# P04_BCS1_Core_Connector.net
KiCad netlist of a schematic drawn in Altium Designer
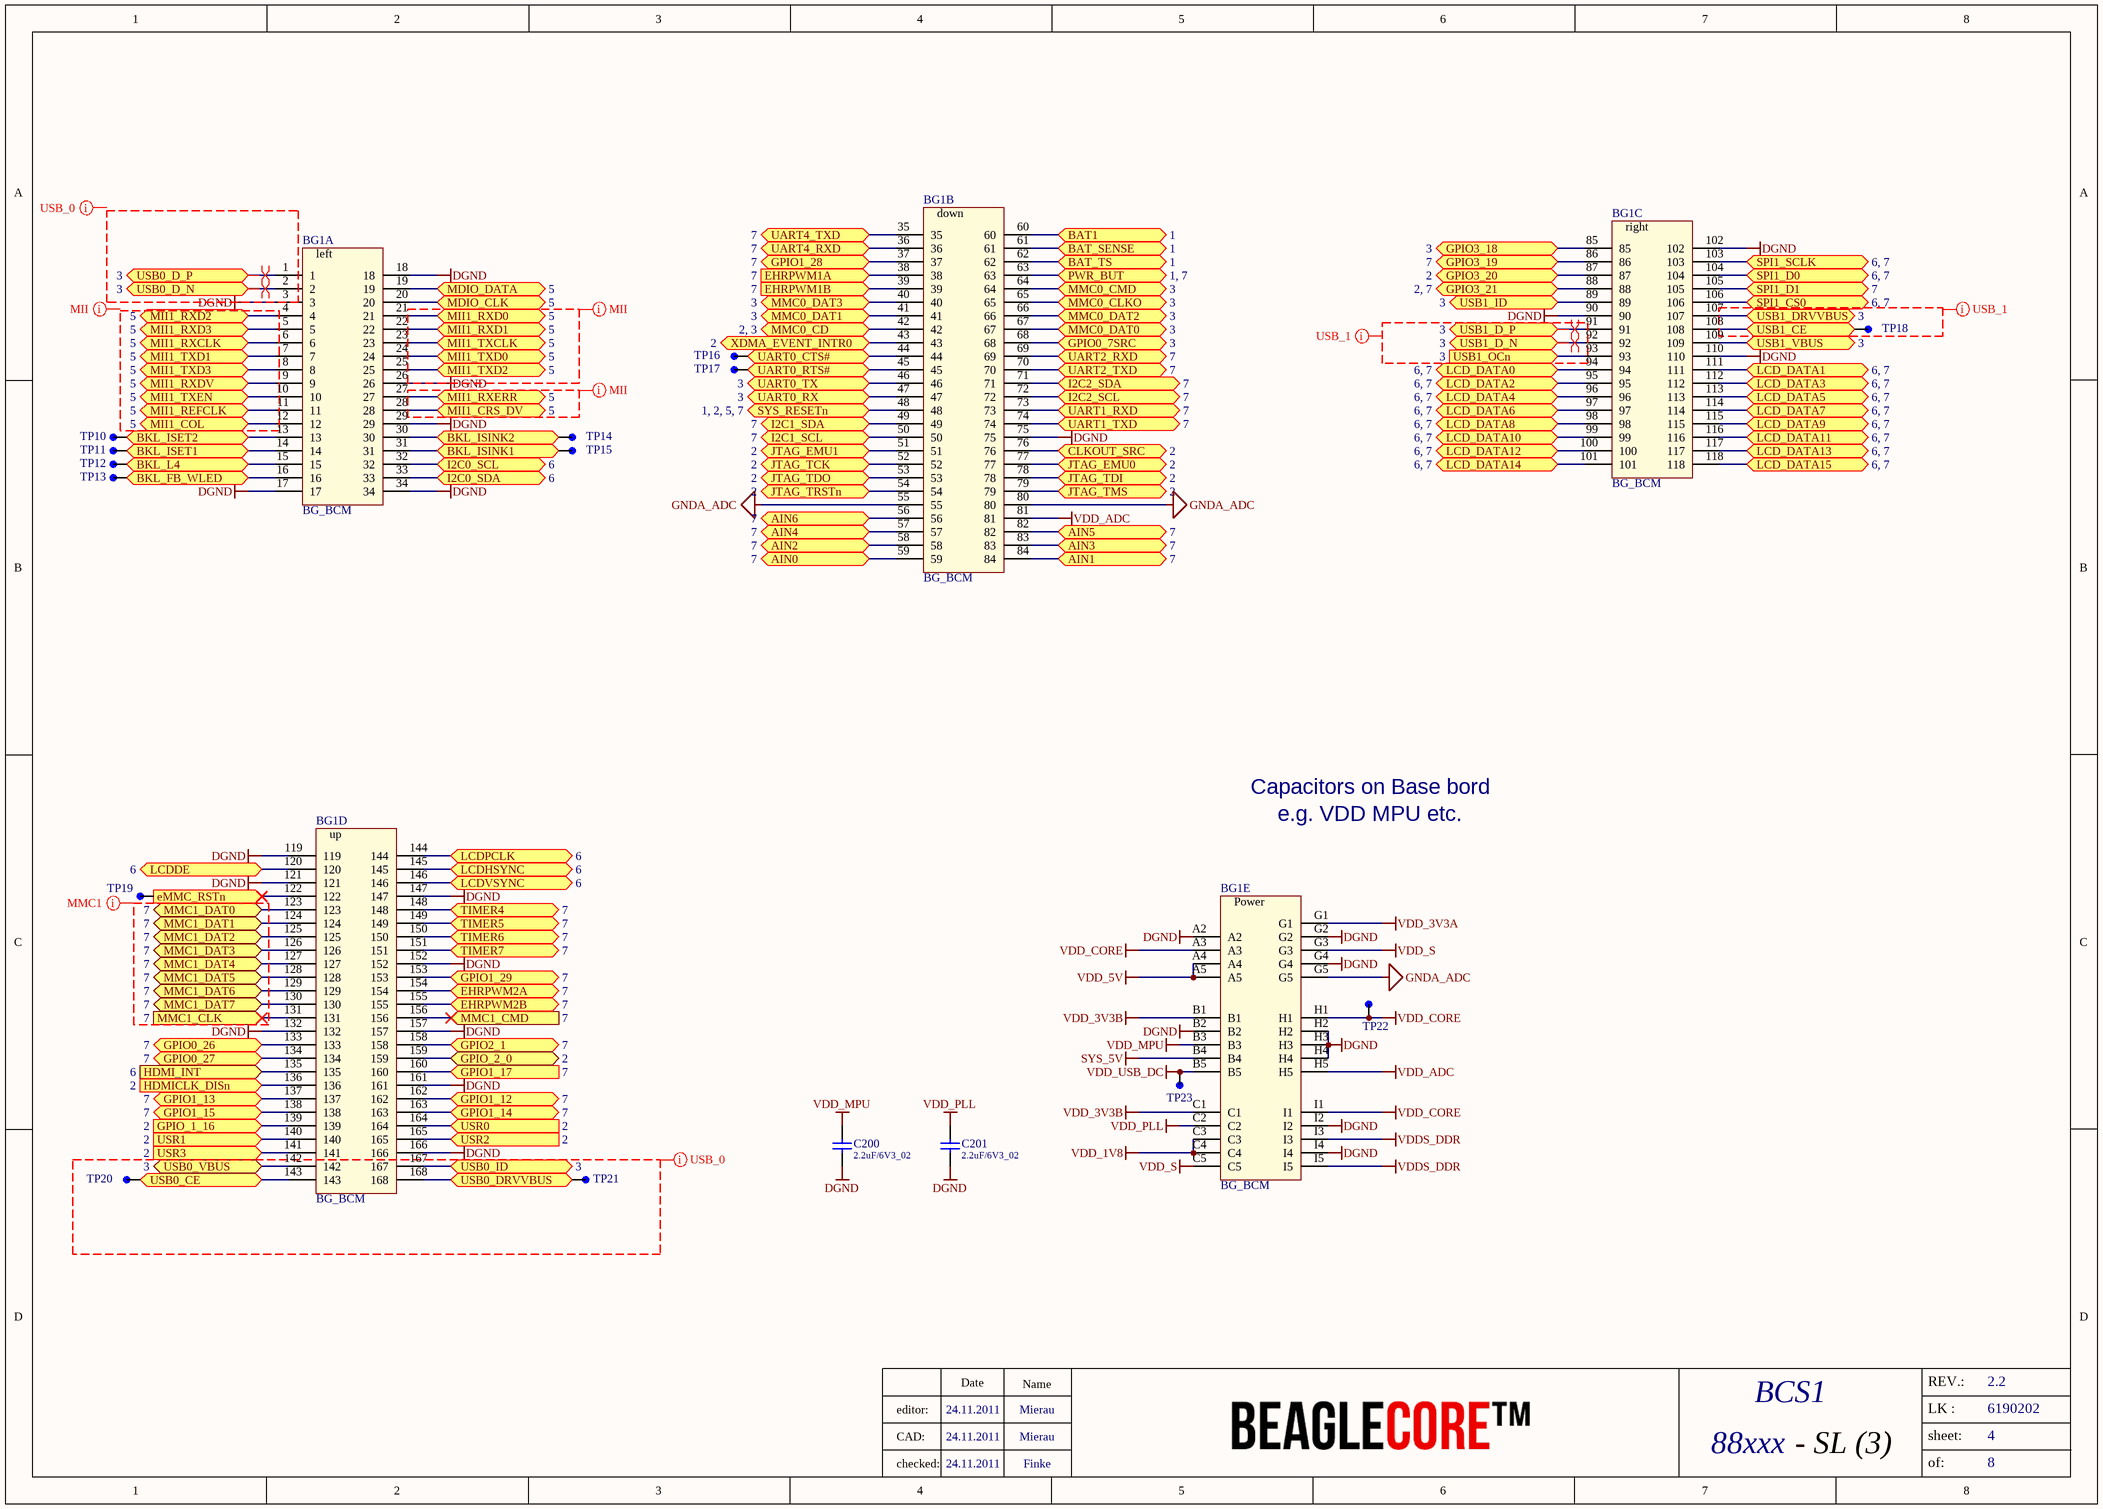
[diagram p0: P04_BCS1_Core Connector.SchDoc]

(export (version "E")
  (design (tool "Eeschema 10.0.6"))
  (components
    (comp (ref "BG1")
      (value "BG_BCM")
      (footprint "BG_BCM")
      (description "Beaglecore")
      (libsource (lib "*") (part "BG_BCM"))
    )
    (comp (ref "C200")
      (value "2.2uF/6V3_02")
      (footprint "CC1005-0402")
      (description "Capacitor 0402;  6V3;  X5R")
      (libsource (lib "*") (part "C2.2uF/6V3_02"))
    )
    (comp (ref "C201")
      (value "2.2uF/6V3_02")
      (footprint "CC1005-0402")
      (description "Capacitor 0402;  6V3;  X5R")
      (libsource (lib "*") (part "C2.2uF/6V3_02"))
    )
    (comp (ref "TP10")
      (value "TP THT")
      (footprint "TP mit 0.8mm Bohrung")
      (description "Testpunkt rund mit Bohrung D=0.8mm")
      (libsource (lib "*") (part "TP1.6 mit Bohrung 0.8"))
    )
    (comp (ref "TP11")
      (value "TP THT")
      (footprint "TP mit 0.8mm Bohrung")
      (description "Testpunkt rund mit Bohrung D=0.8mm")
      (libsource (lib "*") (part "TP1.6 mit Bohrung 0.8"))
    )
    (comp (ref "TP12")
      (value "TP THT")
      (footprint "TP mit 0.8mm Bohrung")
      (description "Testpunkt rund mit Bohrung D=0.8mm")
      (libsource (lib "*") (part "TP1.6 mit Bohrung 0.8"))
    )
    (comp (ref "TP13")
      (value "TP THT")
      (footprint "TP mit 0.8mm Bohrung")
      (description "Testpunkt rund mit Bohrung D=0.8mm")
      (libsource (lib "*") (part "TP1.6 mit Bohrung 0.8"))
    )
    (comp (ref "TP14")
      (value "TP THT")
      (footprint "TP mit 0.8mm Bohrung")
      (description "Testpunkt rund mit Bohrung D=0.8mm")
      (libsource (lib "*") (part "TP1.6 mit Bohrung 0.8"))
    )
    (comp (ref "TP15")
      (value "TP THT")
      (footprint "TP mit 0.8mm Bohrung")
      (description "Testpunkt rund mit Bohrung D=0.8mm")
      (libsource (lib "*") (part "TP1.6 mit Bohrung 0.8"))
    )
    (comp (ref "TP16")
      (value "TP THT")
      (footprint "TP mit 0.8mm Bohrung")
      (description "Testpunkt rund mit Bohrung D=0.8mm")
      (libsource (lib "*") (part "TP1.6 mit Bohrung 0.8"))
    )
    (comp (ref "TP17")
      (value "TP THT")
      (footprint "TP mit 0.8mm Bohrung")
      (description "Testpunkt rund mit Bohrung D=0.8mm")
      (libsource (lib "*") (part "TP1.6 mit Bohrung 0.8"))
    )
    (comp (ref "TP18")
      (value "TP THT")
      (footprint "TP mit 0.8mm Bohrung")
      (description "Testpunkt rund mit Bohrung D=0.8mm")
      (libsource (lib "*") (part "TP1.6 mit Bohrung 0.8"))
    )
    (comp (ref "TP19")
      (value "TP THT")
      (footprint "TP mit 0.8mm Bohrung")
      (description "Testpunkt rund mit Bohrung D=0.8mm")
      (fields (field (name "ERSTELLT VON") "Finke"))
      (libsource (lib "*") (part "TP1.6 mit Bohrung 0.8"))
    )
    (comp (ref "TP20")
      (value "TP THT")
      (footprint "TP mit 0.8mm Bohrung")
      (description "Testpunkt rund mit Bohrung D=0.8mm")
      (libsource (lib "*") (part "TP1.6 mit Bohrung 0.8"))
    )
    (comp (ref "TP21")
      (value "TP THT")
      (footprint "TP mit 0.8mm Bohrung")
      (description "Testpunkt rund mit Bohrung D=0.8mm")
      (libsource (lib "*") (part "TP1.6 mit Bohrung 0.8"))
    )
    (comp (ref "TP22")
      (value "TP THT")
      (footprint "TP mit 0.8mm Bohrung")
      (description "Testpunkt rund mit Bohrung D=0.8mm")
      (libsource (lib "*") (part "TP1.6 mit Bohrung 0.8"))
    )
    (comp (ref "TP23")
      (value "TP THT")
      (footprint "TP mit 0.8mm Bohrung")
      (description "Testpunkt rund mit Bohrung D=0.8mm")
      (libsource (lib "*") (part "TP1.6 mit Bohrung 0.8"))
    )
  )
  (nets
    (net (code "1") (name "/AIN0") (class "Default")
      (node (ref "BG1") (pin "59") (pinfunction "59_59") (pintype "passive"))
    )
    (net (code "2") (name "/AIN1") (class "Default")
      (node (ref "BG1") (pin "84") (pinfunction "84_84") (pintype "passive"))
    )
    (net (code "3") (name "/AIN2") (class "Default")
      (node (ref "BG1") (pin "58") (pinfunction "58_58") (pintype "passive"))
    )
    (net (code "4") (name "/AIN3") (class "Default")
      (node (ref "BG1") (pin "83") (pinfunction "83_83") (pintype "passive"))
    )
    (net (code "5") (name "/AIN4") (class "Default")
      (node (ref "BG1") (pin "57") (pinfunction "57_57") (pintype "passive"))
    )
    (net (code "6") (name "/AIN5") (class "Default")
      (node (ref "BG1") (pin "82") (pinfunction "82_82") (pintype "passive"))
    )
    (net (code "7") (name "/AIN6") (class "Default")
      (node (ref "BG1") (pin "56") (pinfunction "56_56") (pintype "passive"))
    )
    (net (code "8") (name "/BAT1") (class "Default")
      (node (ref "BG1") (pin "60") (pinfunction "60_60") (pintype "passive"))
    )
    (net (code "9") (name "/BAT_SENSE") (class "Default")
      (node (ref "BG1") (pin "61") (pinfunction "61_61") (pintype "passive"))
    )
    (net (code "10") (name "/BAT_TS") (class "Default")
      (node (ref "BG1") (pin "62") (pinfunction "62_62") (pintype "passive"))
    )
    (net (code "11") (name "/BKL_FB_WLED") (class "Default")
      (node (ref "BG1") (pin "16") (pinfunction "16_16") (pintype "passive"))
      (node (ref "TP13") (pin "1") (pinfunction "Pin_1") (pintype "passive"))
    )
    (net (code "12") (name "/BKL_ISET1") (class "Default")
      (node (ref "BG1") (pin "14") (pinfunction "14_14") (pintype "passive"))
      (node (ref "TP11") (pin "1") (pinfunction "Pin_1") (pintype "passive"))
    )
    (net (code "13") (name "/BKL_ISET2") (class "Default")
      (node (ref "BG1") (pin "13") (pinfunction "13_13") (pintype "passive"))
      (node (ref "TP10") (pin "1") (pinfunction "Pin_1") (pintype "passive"))
    )
    (net (code "14") (name "/BKL_ISINK1") (class "Default")
      (node (ref "BG1") (pin "31") (pinfunction "31_31") (pintype "passive"))
      (node (ref "TP15") (pin "1") (pinfunction "Pin_1") (pintype "passive"))
    )
    (net (code "15") (name "/BKL_ISINK2") (class "Default")
      (node (ref "BG1") (pin "30") (pinfunction "30_30") (pintype "passive"))
      (node (ref "TP14") (pin "1") (pinfunction "Pin_1") (pintype "passive"))
    )
    (net (code "16") (name "/BKL_L4") (class "Default")
      (node (ref "BG1") (pin "15") (pinfunction "15_15") (pintype "passive"))
      (node (ref "TP12") (pin "1") (pinfunction "Pin_1") (pintype "passive"))
    )
    (net (code "17") (name "/CLKOUT_SRC") (class "Default")
      (node (ref "BG1") (pin "76") (pinfunction "76_76") (pintype "passive"))
    )
    (net (code "18") (name "/EHRPWM1A") (class "Default")
      (node (ref "BG1") (pin "38") (pinfunction "38_38") (pintype "passive"))
    )
    (net (code "19") (name "/EHRPWM1B") (class "Default")
      (node (ref "BG1") (pin "39") (pinfunction "39_39") (pintype "passive"))
    )
    (net (code "20") (name "/EHRPWM2A") (class "Default")
      (node (ref "BG1") (pin "154") (pinfunction "154_154") (pintype "passive"))
    )
    (net (code "21") (name "/EHRPWM2B") (class "Default")
      (node (ref "BG1") (pin "155") (pinfunction "155_155") (pintype "passive"))
    )
    (net (code "22") (name "/GPIO0_7SRC") (class "Default")
      (node (ref "BG1") (pin "68") (pinfunction "68_68") (pintype "passive"))
    )
    (net (code "23") (name "/GPIO0_26") (class "Default")
      (node (ref "BG1") (pin "133") (pinfunction "133_133") (pintype "passive"))
    )
    (net (code "24") (name "/GPIO0_27") (class "Default")
      (node (ref "BG1") (pin "134") (pinfunction "134_134") (pintype "passive"))
    )
    (net (code "25") (name "/GPIO1_12") (class "Default")
      (node (ref "BG1") (pin "162") (pinfunction "162_162") (pintype "passive"))
    )
    (net (code "26") (name "/GPIO1_13") (class "Default")
      (node (ref "BG1") (pin "137") (pinfunction "137_137") (pintype "passive"))
    )
    (net (code "27") (name "/GPIO1_14") (class "Default")
      (node (ref "BG1") (pin "163") (pinfunction "163_163") (pintype "passive"))
    )
    (net (code "28") (name "/GPIO1_15") (class "Default")
      (node (ref "BG1") (pin "138") (pinfunction "138_138") (pintype "passive"))
    )
    (net (code "29") (name "/GPIO1_17") (class "Default")
      (node (ref "BG1") (pin "160") (pinfunction "160_160") (pintype "passive"))
    )
    (net (code "30") (name "/GPIO1_28") (class "Default")
      (node (ref "BG1") (pin "37") (pinfunction "37_37") (pintype "passive"))
    )
    (net (code "31") (name "/GPIO1_29") (class "Default")
      (node (ref "BG1") (pin "153") (pinfunction "153_153") (pintype "passive"))
    )
    (net (code "32") (name "/GPIO2_1") (class "Default")
      (node (ref "BG1") (pin "158") (pinfunction "158_158") (pintype "passive"))
    )
    (net (code "33") (name "/GPIO3_18") (class "Default")
      (node (ref "BG1") (pin "85") (pinfunction "85_85") (pintype "passive"))
    )
    (net (code "34") (name "/GPIO3_19") (class "Default")
      (node (ref "BG1") (pin "86") (pinfunction "86_86") (pintype "passive"))
    )
    (net (code "35") (name "/GPIO3_20") (class "Default")
      (node (ref "BG1") (pin "87") (pinfunction "87_87") (pintype "passive"))
    )
    (net (code "36") (name "/GPIO3_21") (class "Default")
      (node (ref "BG1") (pin "88") (pinfunction "88_88") (pintype "passive"))
    )
    (net (code "37") (name "/GPIO_1_16") (class "Default")
      (node (ref "BG1") (pin "139") (pinfunction "139_139") (pintype "passive"))
    )
    (net (code "38") (name "/GPIO_2_0") (class "Default")
      (node (ref "BG1") (pin "159") (pinfunction "159_159") (pintype "passive"))
    )
    (net (code "39") (name "/HDMICLK_DISn") (class "Default")
      (node (ref "BG1") (pin "136") (pinfunction "136_136") (pintype "passive"))
    )
    (net (code "40") (name "/HDMI_INT") (class "Default")
      (node (ref "BG1") (pin "135") (pinfunction "135_135") (pintype "passive"))
    )
    (net (code "41") (name "/I2C0_SCL") (class "Default")
      (node (ref "BG1") (pin "32") (pinfunction "32_32") (pintype "passive"))
    )
    (net (code "42") (name "/I2C0_SDA") (class "Default")
      (node (ref "BG1") (pin "33") (pinfunction "33_33") (pintype "passive"))
    )
    (net (code "43") (name "/I2C1_SCL") (class "Default")
      (node (ref "BG1") (pin "50") (pinfunction "50_50") (pintype "passive"))
    )
    (net (code "44") (name "/I2C1_SDA") (class "Default")
      (node (ref "BG1") (pin "49") (pinfunction "49_49") (pintype "passive"))
    )
    (net (code "45") (name "/I2C2_SCL") (class "Default")
      (node (ref "BG1") (pin "72") (pinfunction "72_72") (pintype "passive"))
    )
    (net (code "46") (name "/I2C2_SDA") (class "Default")
      (node (ref "BG1") (pin "71") (pinfunction "71_71") (pintype "passive"))
    )
    (net (code "47") (name "/JTAG_EMU0") (class "Default")
      (node (ref "BG1") (pin "77") (pinfunction "77_77") (pintype "passive"))
    )
    (net (code "48") (name "/JTAG_EMU1") (class "Default")
      (node (ref "BG1") (pin "51") (pinfunction "51_51") (pintype "passive"))
    )
    (net (code "49") (name "/JTAG_TCK") (class "Default")
      (node (ref "BG1") (pin "52") (pinfunction "52_52") (pintype "passive"))
    )
    (net (code "50") (name "/JTAG_TDI") (class "Default")
      (node (ref "BG1") (pin "78") (pinfunction "78_78") (pintype "passive"))
    )
    (net (code "51") (name "/JTAG_TDO") (class "Default")
      (node (ref "BG1") (pin "53") (pinfunction "53_53") (pintype "passive"))
    )
    (net (code "52") (name "/JTAG_TMS") (class "Default")
      (node (ref "BG1") (pin "79") (pinfunction "79_79") (pintype "passive"))
    )
    (net (code "53") (name "/JTAG_TRSTn") (class "Default")
      (node (ref "BG1") (pin "54") (pinfunction "54_54") (pintype "passive"))
    )
    (net (code "54") (name "/LCDDE") (class "Default")
      (node (ref "BG1") (pin "120") (pinfunction "120_120") (pintype "passive"))
    )
    (net (code "55") (name "/LCDHSYNC") (class "Default")
      (node (ref "BG1") (pin "145") (pinfunction "145_145") (pintype "passive"))
    )
    (net (code "56") (name "/LCDPCLK") (class "Default")
      (node (ref "BG1") (pin "144") (pinfunction "144_144") (pintype "passive"))
    )
    (net (code "57") (name "/LCDVSYNC") (class "Default")
      (node (ref "BG1") (pin "146") (pinfunction "146_146") (pintype "passive"))
    )
    (net (code "58") (name "/LCD_DATA0") (class "Default")
      (node (ref "BG1") (pin "94") (pinfunction "94_94") (pintype "passive"))
    )
    (net (code "59") (name "/LCD_DATA1") (class "Default")
      (node (ref "BG1") (pin "111") (pinfunction "111_111") (pintype "passive"))
    )
    (net (code "60") (name "/LCD_DATA2") (class "Default")
      (node (ref "BG1") (pin "95") (pinfunction "95_95") (pintype "passive"))
    )
    (net (code "61") (name "/LCD_DATA3") (class "Default")
      (node (ref "BG1") (pin "112") (pinfunction "112_112") (pintype "passive"))
    )
    (net (code "62") (name "/LCD_DATA4") (class "Default")
      (node (ref "BG1") (pin "96") (pinfunction "96_96") (pintype "passive"))
    )
    (net (code "63") (name "/LCD_DATA5") (class "Default")
      (node (ref "BG1") (pin "113") (pinfunction "113_113") (pintype "passive"))
    )
    (net (code "64") (name "/LCD_DATA6") (class "Default")
      (node (ref "BG1") (pin "97") (pinfunction "97_97") (pintype "passive"))
    )
    (net (code "65") (name "/LCD_DATA7") (class "Default")
      (node (ref "BG1") (pin "114") (pinfunction "114_114") (pintype "passive"))
    )
    (net (code "66") (name "/LCD_DATA8") (class "Default")
      (node (ref "BG1") (pin "98") (pinfunction "98_98") (pintype "passive"))
    )
    (net (code "67") (name "/LCD_DATA9") (class "Default")
      (node (ref "BG1") (pin "115") (pinfunction "115_115") (pintype "passive"))
    )
    (net (code "68") (name "/LCD_DATA10") (class "Default")
      (node (ref "BG1") (pin "99") (pinfunction "99_99") (pintype "passive"))
    )
    (net (code "69") (name "/LCD_DATA11") (class "Default")
      (node (ref "BG1") (pin "116") (pinfunction "116_116") (pintype "passive"))
    )
    (net (code "70") (name "/LCD_DATA12") (class "Default")
      (node (ref "BG1") (pin "100") (pinfunction "100_100") (pintype "passive"))
    )
    (net (code "71") (name "/LCD_DATA13") (class "Default")
      (node (ref "BG1") (pin "117") (pinfunction "117_117") (pintype "passive"))
    )
    (net (code "72") (name "/LCD_DATA14") (class "Default")
      (node (ref "BG1") (pin "101") (pinfunction "101_101") (pintype "passive"))
    )
    (net (code "73") (name "/LCD_DATA15") (class "Default")
      (node (ref "BG1") (pin "118") (pinfunction "118_118") (pintype "passive"))
    )
    (net (code "74") (name "/MDIO_CLK") (class "Default")
      (node (ref "BG1") (pin "20") (pinfunction "20_20") (pintype "passive"))
    )
    (net (code "75") (name "/MDIO_DATA") (class "Default")
      (node (ref "BG1") (pin "19") (pinfunction "19_19") (pintype "passive"))
    )
    (net (code "76") (name "/MII1_COL") (class "Default")
      (node (ref "BG1") (pin "12") (pinfunction "12_12") (pintype "passive"))
    )
    (net (code "77") (name "/MII1_CRS_DV") (class "Default")
      (node (ref "BG1") (pin "28") (pinfunction "28_28") (pintype "passive"))
    )
    (net (code "78") (name "/MII1_REFCLK") (class "Default")
      (node (ref "BG1") (pin "11") (pinfunction "11_11") (pintype "passive"))
    )
    (net (code "79") (name "/MII1_RXCLK") (class "Default")
      (node (ref "BG1") (pin "6") (pinfunction "6_6") (pintype "passive"))
    )
    (net (code "80") (name "/MII1_RXD0") (class "Default")
      (node (ref "BG1") (pin "21") (pinfunction "21_21") (pintype "passive"))
    )
    (net (code "81") (name "/MII1_RXD1") (class "Default")
      (node (ref "BG1") (pin "22") (pinfunction "22_22") (pintype "passive"))
    )
    (net (code "82") (name "/MII1_RXD2") (class "Default")
      (node (ref "BG1") (pin "4") (pinfunction "4_4") (pintype "passive"))
    )
    (net (code "83") (name "/MII1_RXD3") (class "Default")
      (node (ref "BG1") (pin "5") (pinfunction "5_5") (pintype "passive"))
    )
    (net (code "84") (name "/MII1_RXDV") (class "Default")
      (node (ref "BG1") (pin "9") (pinfunction "9_9") (pintype "passive"))
    )
    (net (code "85") (name "/MII1_RXERR") (class "Default")
      (node (ref "BG1") (pin "27") (pinfunction "27_27") (pintype "passive"))
    )
    (net (code "86") (name "/MII1_TXCLK") (class "Default")
      (node (ref "BG1") (pin "23") (pinfunction "23_23") (pintype "passive"))
    )
    (net (code "87") (name "/MII1_TXD0") (class "Default")
      (node (ref "BG1") (pin "24") (pinfunction "24_24") (pintype "passive"))
    )
    (net (code "88") (name "/MII1_TXD1") (class "Default")
      (node (ref "BG1") (pin "7") (pinfunction "7_7") (pintype "passive"))
    )
    (net (code "89") (name "/MII1_TXD2") (class "Default")
      (node (ref "BG1") (pin "25") (pinfunction "25_25") (pintype "passive"))
    )
    (net (code "90") (name "/MII1_TXD3") (class "Default")
      (node (ref "BG1") (pin "8") (pinfunction "8_8") (pintype "passive"))
    )
    (net (code "91") (name "/MII1_TXEN") (class "Default")
      (node (ref "BG1") (pin "10") (pinfunction "10_10") (pintype "passive"))
    )
    (net (code "92") (name "/MMC0_CD") (class "Default")
      (node (ref "BG1") (pin "42") (pinfunction "42_42") (pintype "passive"))
    )
    (net (code "93") (name "/MMC0_CLKO") (class "Default")
      (node (ref "BG1") (pin "65") (pinfunction "65_65") (pintype "passive"))
    )
    (net (code "94") (name "/MMC0_CMD") (class "Default")
      (node (ref "BG1") (pin "64") (pinfunction "64_64") (pintype "passive"))
    )
    (net (code "95") (name "/MMC0_DAT0") (class "Default")
      (node (ref "BG1") (pin "67") (pinfunction "67_67") (pintype "passive"))
    )
    (net (code "96") (name "/MMC0_DAT1") (class "Default")
      (node (ref "BG1") (pin "41") (pinfunction "41_41") (pintype "passive"))
    )
    (net (code "97") (name "/MMC0_DAT2") (class "Default")
      (node (ref "BG1") (pin "66") (pinfunction "66_66") (pintype "passive"))
    )
    (net (code "98") (name "/MMC0_DAT3") (class "Default")
      (node (ref "BG1") (pin "40") (pinfunction "40_40") (pintype "passive"))
    )
    (net (code "99") (name "/MMC1_CLK") (class "Default")
      (node (ref "BG1") (pin "131") (pinfunction "131_131") (pintype "passive+no_connect"))
    )
    (net (code "100") (name "/MMC1_CMD") (class "Default")
      (node (ref "BG1") (pin "156") (pinfunction "156_156") (pintype "passive+no_connect"))
    )
    (net (code "101") (name "/MMC1_DAT0") (class "Default")
      (node (ref "BG1") (pin "123") (pinfunction "123_123") (pintype "passive"))
    )
    (net (code "102") (name "/MMC1_DAT1") (class "Default")
      (node (ref "BG1") (pin "124") (pinfunction "124_124") (pintype "passive"))
    )
    (net (code "103") (name "/MMC1_DAT2") (class "Default")
      (node (ref "BG1") (pin "125") (pinfunction "125_125") (pintype "passive"))
    )
    (net (code "104") (name "/MMC1_DAT3") (class "Default")
      (node (ref "BG1") (pin "126") (pinfunction "126_126") (pintype "passive"))
    )
    (net (code "105") (name "/MMC1_DAT4") (class "Default")
      (node (ref "BG1") (pin "127") (pinfunction "127_127") (pintype "passive"))
    )
    (net (code "106") (name "/MMC1_DAT5") (class "Default")
      (node (ref "BG1") (pin "128") (pinfunction "128_128") (pintype "passive"))
    )
    (net (code "107") (name "/MMC1_DAT6") (class "Default")
      (node (ref "BG1") (pin "129") (pinfunction "129_129") (pintype "passive"))
    )
    (net (code "108") (name "/MMC1_DAT7") (class "Default")
      (node (ref "BG1") (pin "130") (pinfunction "130_130") (pintype "passive"))
    )
    (net (code "109") (name "/PWR_BUT") (class "Default")
      (node (ref "BG1") (pin "63") (pinfunction "63_63") (pintype "passive"))
    )
    (net (code "110") (name "/SPI1_CS0") (class "Default")
      (node (ref "BG1") (pin "106") (pinfunction "106_106") (pintype "passive"))
    )
    (net (code "111") (name "/SPI1_D0") (class "Default")
      (node (ref "BG1") (pin "104") (pinfunction "104_104") (pintype "passive"))
    )
    (net (code "112") (name "/SPI1_D1") (class "Default")
      (node (ref "BG1") (pin "105") (pinfunction "105_105") (pintype "passive"))
    )
    (net (code "113") (name "/SPI1_SCLK") (class "Default")
      (node (ref "BG1") (pin "103") (pinfunction "103_103") (pintype "passive"))
    )
    (net (code "114") (name "/SYS_RESETn") (class "Default")
      (node (ref "BG1") (pin "48") (pinfunction "48_48") (pintype "passive"))
    )
    (net (code "115") (name "/TIMER4") (class "Default")
      (node (ref "BG1") (pin "148") (pinfunction "148_148") (pintype "passive"))
    )
    (net (code "116") (name "/TIMER5") (class "Default")
      (node (ref "BG1") (pin "149") (pinfunction "149_149") (pintype "passive"))
    )
    (net (code "117") (name "/TIMER6") (class "Default")
      (node (ref "BG1") (pin "150") (pinfunction "150_150") (pintype "passive"))
    )
    (net (code "118") (name "/TIMER7") (class "Default")
      (node (ref "BG1") (pin "151") (pinfunction "151_151") (pintype "passive"))
    )
    (net (code "119") (name "/UART0_CTS#") (class "Default")
      (node (ref "BG1") (pin "44") (pinfunction "44_44") (pintype "passive"))
      (node (ref "TP16") (pin "1") (pinfunction "Pin_1") (pintype "passive"))
    )
    (net (code "120") (name "/UART0_RTS#") (class "Default")
      (node (ref "BG1") (pin "45") (pinfunction "45_45") (pintype "passive"))
      (node (ref "TP17") (pin "1") (pinfunction "Pin_1") (pintype "passive"))
    )
    (net (code "121") (name "/UART0_RX") (class "Default")
      (node (ref "BG1") (pin "47") (pinfunction "47_47") (pintype "passive"))
    )
    (net (code "122") (name "/UART0_TX") (class "Default")
      (node (ref "BG1") (pin "46") (pinfunction "46_46") (pintype "passive"))
    )
    (net (code "123") (name "/UART1_RXD") (class "Default")
      (node (ref "BG1") (pin "73") (pinfunction "73_73") (pintype "passive"))
    )
    (net (code "124") (name "/UART1_TXD") (class "Default")
      (node (ref "BG1") (pin "74") (pinfunction "74_74") (pintype "passive"))
    )
    (net (code "125") (name "/UART2_RXD") (class "Default")
      (node (ref "BG1") (pin "69") (pinfunction "69_69") (pintype "passive"))
    )
    (net (code "126") (name "/UART2_TXD") (class "Default")
      (node (ref "BG1") (pin "70") (pinfunction "70_70") (pintype "passive"))
    )
    (net (code "127") (name "/UART4_RXD") (class "Default")
      (node (ref "BG1") (pin "36") (pinfunction "36_36") (pintype "passive"))
    )
    (net (code "128") (name "/UART4_TXD") (class "Default")
      (node (ref "BG1") (pin "35") (pinfunction "35_35") (pintype "passive"))
    )
    (net (code "129") (name "/USB0_CE") (class "Default")
      (node (ref "BG1") (pin "143") (pinfunction "143_143") (pintype "passive"))
      (node (ref "TP20") (pin "1") (pinfunction "Pin_1") (pintype "passive"))
    )
    (net (code "130") (name "/USB0_DRVVBUS") (class "Default")
      (node (ref "BG1") (pin "168") (pinfunction "168_168") (pintype "passive"))
      (node (ref "TP21") (pin "1") (pinfunction "Pin_1") (pintype "passive"))
    )
    (net (code "131") (name "/USB0_D_N") (class "Default")
      (node (ref "BG1") (pin "2") (pinfunction "2_2") (pintype "passive"))
    )
    (net (code "132") (name "/USB0_D_P") (class "Default")
      (node (ref "BG1") (pin "1") (pinfunction "1_1") (pintype "passive"))
    )
    (net (code "133") (name "/USB0_ID") (class "Default")
      (node (ref "BG1") (pin "167") (pinfunction "167_167") (pintype "passive"))
    )
    (net (code "134") (name "/USB0_VBUS") (class "Default")
      (node (ref "BG1") (pin "142") (pinfunction "142_142") (pintype "passive"))
    )
    (net (code "135") (name "/USB1_CE") (class "Default")
      (node (ref "BG1") (pin "108") (pinfunction "108_108") (pintype "passive"))
      (node (ref "TP18") (pin "1") (pinfunction "Pin_1") (pintype "passive"))
    )
    (net (code "136") (name "/USB1_DRVVBUS") (class "Default")
      (node (ref "BG1") (pin "107") (pinfunction "107_107") (pintype "passive"))
    )
    (net (code "137") (name "/USB1_D_N") (class "Default")
      (node (ref "BG1") (pin "92") (pinfunction "92_92") (pintype "passive"))
    )
    (net (code "138") (name "/USB1_D_P") (class "Default")
      (node (ref "BG1") (pin "91") (pinfunction "91_91") (pintype "passive"))
    )
    (net (code "139") (name "/USB1_ID") (class "Default")
      (node (ref "BG1") (pin "89") (pinfunction "89_89") (pintype "passive"))
    )
    (net (code "140") (name "/USB1_OCn") (class "Default")
      (node (ref "BG1") (pin "93") (pinfunction "93_93") (pintype "passive"))
    )
    (net (code "141") (name "/USB1_VBUS") (class "Default")
      (node (ref "BG1") (pin "109") (pinfunction "109_109") (pintype "passive"))
    )
    (net (code "142") (name "/USR0") (class "Default")
      (node (ref "BG1") (pin "164") (pinfunction "164_164") (pintype "passive"))
    )
    (net (code "143") (name "/USR1") (class "Default")
      (node (ref "BG1") (pin "140") (pinfunction "140_140") (pintype "passive"))
    )
    (net (code "144") (name "/USR2") (class "Default")
      (node (ref "BG1") (pin "165") (pinfunction "165_165") (pintype "passive"))
    )
    (net (code "145") (name "/USR3") (class "Default")
      (node (ref "BG1") (pin "141") (pinfunction "141_141") (pintype "passive"))
    )
    (net (code "146") (name "/XDMA_EVENT_INTR0") (class "Default")
      (node (ref "BG1") (pin "43") (pinfunction "43_43") (pintype "passive"))
    )
    (net (code "147") (name "/eMMC_RSTn") (class "Default")
      (node (ref "BG1") (pin "122") (pinfunction "122_122") (pintype "passive"))
      (node (ref "TP19") (pin "1") (pinfunction "Pin_1") (pintype "passive"))
    )
    (net (code "148") (name "DGND") (class "Default")
      (node (ref "BG1") (pin "102") (pinfunction "102_102") (pintype "passive"))
      (node (ref "BG1") (pin "110") (pinfunction "110_110") (pintype "passive"))
      (node (ref "BG1") (pin "119") (pinfunction "119_119") (pintype "passive"))
      (node (ref "BG1") (pin "121") (pinfunction "121_121") (pintype "passive"))
      (node (ref "BG1") (pin "132") (pinfunction "132_132") (pintype "passive"))
      (node (ref "BG1") (pin "147") (pinfunction "147_147") (pintype "passive"))
      (node (ref "BG1") (pin "152") (pinfunction "152_152") (pintype "passive"))
      (node (ref "BG1") (pin "157") (pinfunction "157_157") (pintype "passive"))
      (node (ref "BG1") (pin "161") (pinfunction "161_161") (pintype "passive"))
      (node (ref "BG1") (pin "166") (pinfunction "166_166") (pintype "passive"))
      (node (ref "BG1") (pin "17") (pinfunction "17_17") (pintype "passive"))
      (node (ref "BG1") (pin "18") (pinfunction "18_18") (pintype "passive"))
      (node (ref "BG1") (pin "26") (pinfunction "26_26") (pintype "passive"))
      (node (ref "BG1") (pin "29") (pinfunction "29_29") (pintype "passive"))
      (node (ref "BG1") (pin "3") (pinfunction "3_3") (pintype "passive"))
      (node (ref "BG1") (pin "34") (pinfunction "34_34") (pintype "passive"))
      (node (ref "BG1") (pin "75") (pinfunction "75_75") (pintype "passive"))
      (node (ref "BG1") (pin "90") (pinfunction "90_90") (pintype "passive"))
      (node (ref "BG1") (pin "A2") (pinfunction "A2_A2") (pintype "passive"))
      (node (ref "BG1") (pin "B2") (pinfunction "B2_B2") (pintype "passive"))
      (node (ref "BG1") (pin "G2") (pinfunction "G2_G2") (pintype "passive"))
      (node (ref "BG1") (pin "G4") (pinfunction "G4_G4") (pintype "passive"))
      (node (ref "BG1") (pin "H2") (pinfunction "H2_H2") (pintype "passive"))
      (node (ref "BG1") (pin "H3") (pinfunction "H3_H3") (pintype "passive"))
      (node (ref "BG1") (pin "H4") (pinfunction "H4_H4") (pintype "passive"))
      (node (ref "BG1") (pin "I2") (pinfunction "I2_I2") (pintype "passive"))
      (node (ref "BG1") (pin "I4") (pinfunction "I4_I4") (pintype "passive"))
      (node (ref "C200") (pin "1") (pinfunction "1_1") (pintype "passive"))
      (node (ref "C201") (pin "1") (pinfunction "1_1") (pintype "passive"))
    )
    (net (code "149") (name "GNDA_ADC") (class "Default")
      (node (ref "BG1") (pin "55") (pinfunction "55_55") (pintype "passive"))
      (node (ref "BG1") (pin "80") (pinfunction "80_80") (pintype "passive"))
      (node (ref "BG1") (pin "G5") (pinfunction "G5_G5") (pintype "passive"))
    )
    (net (code "150") (name "SYS_5V") (class "Default")
      (node (ref "BG1") (pin "B4") (pinfunction "B4_B4") (pintype "passive"))
    )
    (net (code "151") (name "VDDS_DDR") (class "Default")
      (node (ref "BG1") (pin "I3") (pinfunction "I3_I3") (pintype "passive"))
      (node (ref "BG1") (pin "I5") (pinfunction "I5_I5") (pintype "passive"))
    )
    (net (code "152") (name "VDD_1V8") (class "Default")
      (node (ref "BG1") (pin "C3") (pinfunction "C3_C3") (pintype "passive"))
      (node (ref "BG1") (pin "C4") (pinfunction "C4_C4") (pintype "passive"))
    )
    (net (code "153") (name "VDD_3V3A") (class "Default")
      (node (ref "BG1") (pin "G1") (pinfunction "G1_G1") (pintype "passive"))
    )
    (net (code "154") (name "VDD_3V3B") (class "Default")
      (node (ref "BG1") (pin "B1") (pinfunction "B1_B1") (pintype "passive"))
      (node (ref "BG1") (pin "C1") (pinfunction "C1_C1") (pintype "passive"))
    )
    (net (code "155") (name "VDD_5V") (class "Default")
      (node (ref "BG1") (pin "A4") (pinfunction "A4_A4") (pintype "passive"))
      (node (ref "BG1") (pin "A5") (pinfunction "A5_A5") (pintype "passive"))
    )
    (net (code "156") (name "VDD_ADC") (class "Default")
      (node (ref "BG1") (pin "81") (pinfunction "81_81") (pintype "passive"))
      (node (ref "BG1") (pin "H5") (pinfunction "H5_H5") (pintype "passive"))
    )
    (net (code "157") (name "VDD_CORE") (class "Default")
      (node (ref "BG1") (pin "A3") (pinfunction "A3_A3") (pintype "passive"))
      (node (ref "BG1") (pin "H1") (pinfunction "H1_H1") (pintype "passive"))
      (node (ref "BG1") (pin "I1") (pinfunction "I1_I1") (pintype "passive"))
      (node (ref "TP22") (pin "1") (pinfunction "Pin_1") (pintype "passive"))
    )
    (net (code "158") (name "VDD_MPU") (class "Default")
      (node (ref "BG1") (pin "B3") (pinfunction "B3_B3") (pintype "passive"))
      (node (ref "C200") (pin "2") (pinfunction "2_2") (pintype "passive"))
    )
    (net (code "159") (name "VDD_PLL") (class "Default")
      (node (ref "BG1") (pin "C2") (pinfunction "C2_C2") (pintype "passive"))
      (node (ref "C201") (pin "2") (pinfunction "2_2") (pintype "passive"))
    )
    (net (code "160") (name "VDD_S") (class "Default")
      (node (ref "BG1") (pin "C5") (pinfunction "C5_C5") (pintype "passive"))
      (node (ref "BG1") (pin "G3") (pinfunction "G3_G3") (pintype "passive"))
    )
    (net (code "161") (name "VDD_USB_DC") (class "Default")
      (node (ref "BG1") (pin "B5") (pinfunction "B5_B5") (pintype "passive"))
      (node (ref "TP23") (pin "1") (pinfunction "Pin_1") (pintype "passive"))
    )
  )
)
